# shem.net
KiCad netlist of a schematic drawn in EAGLE
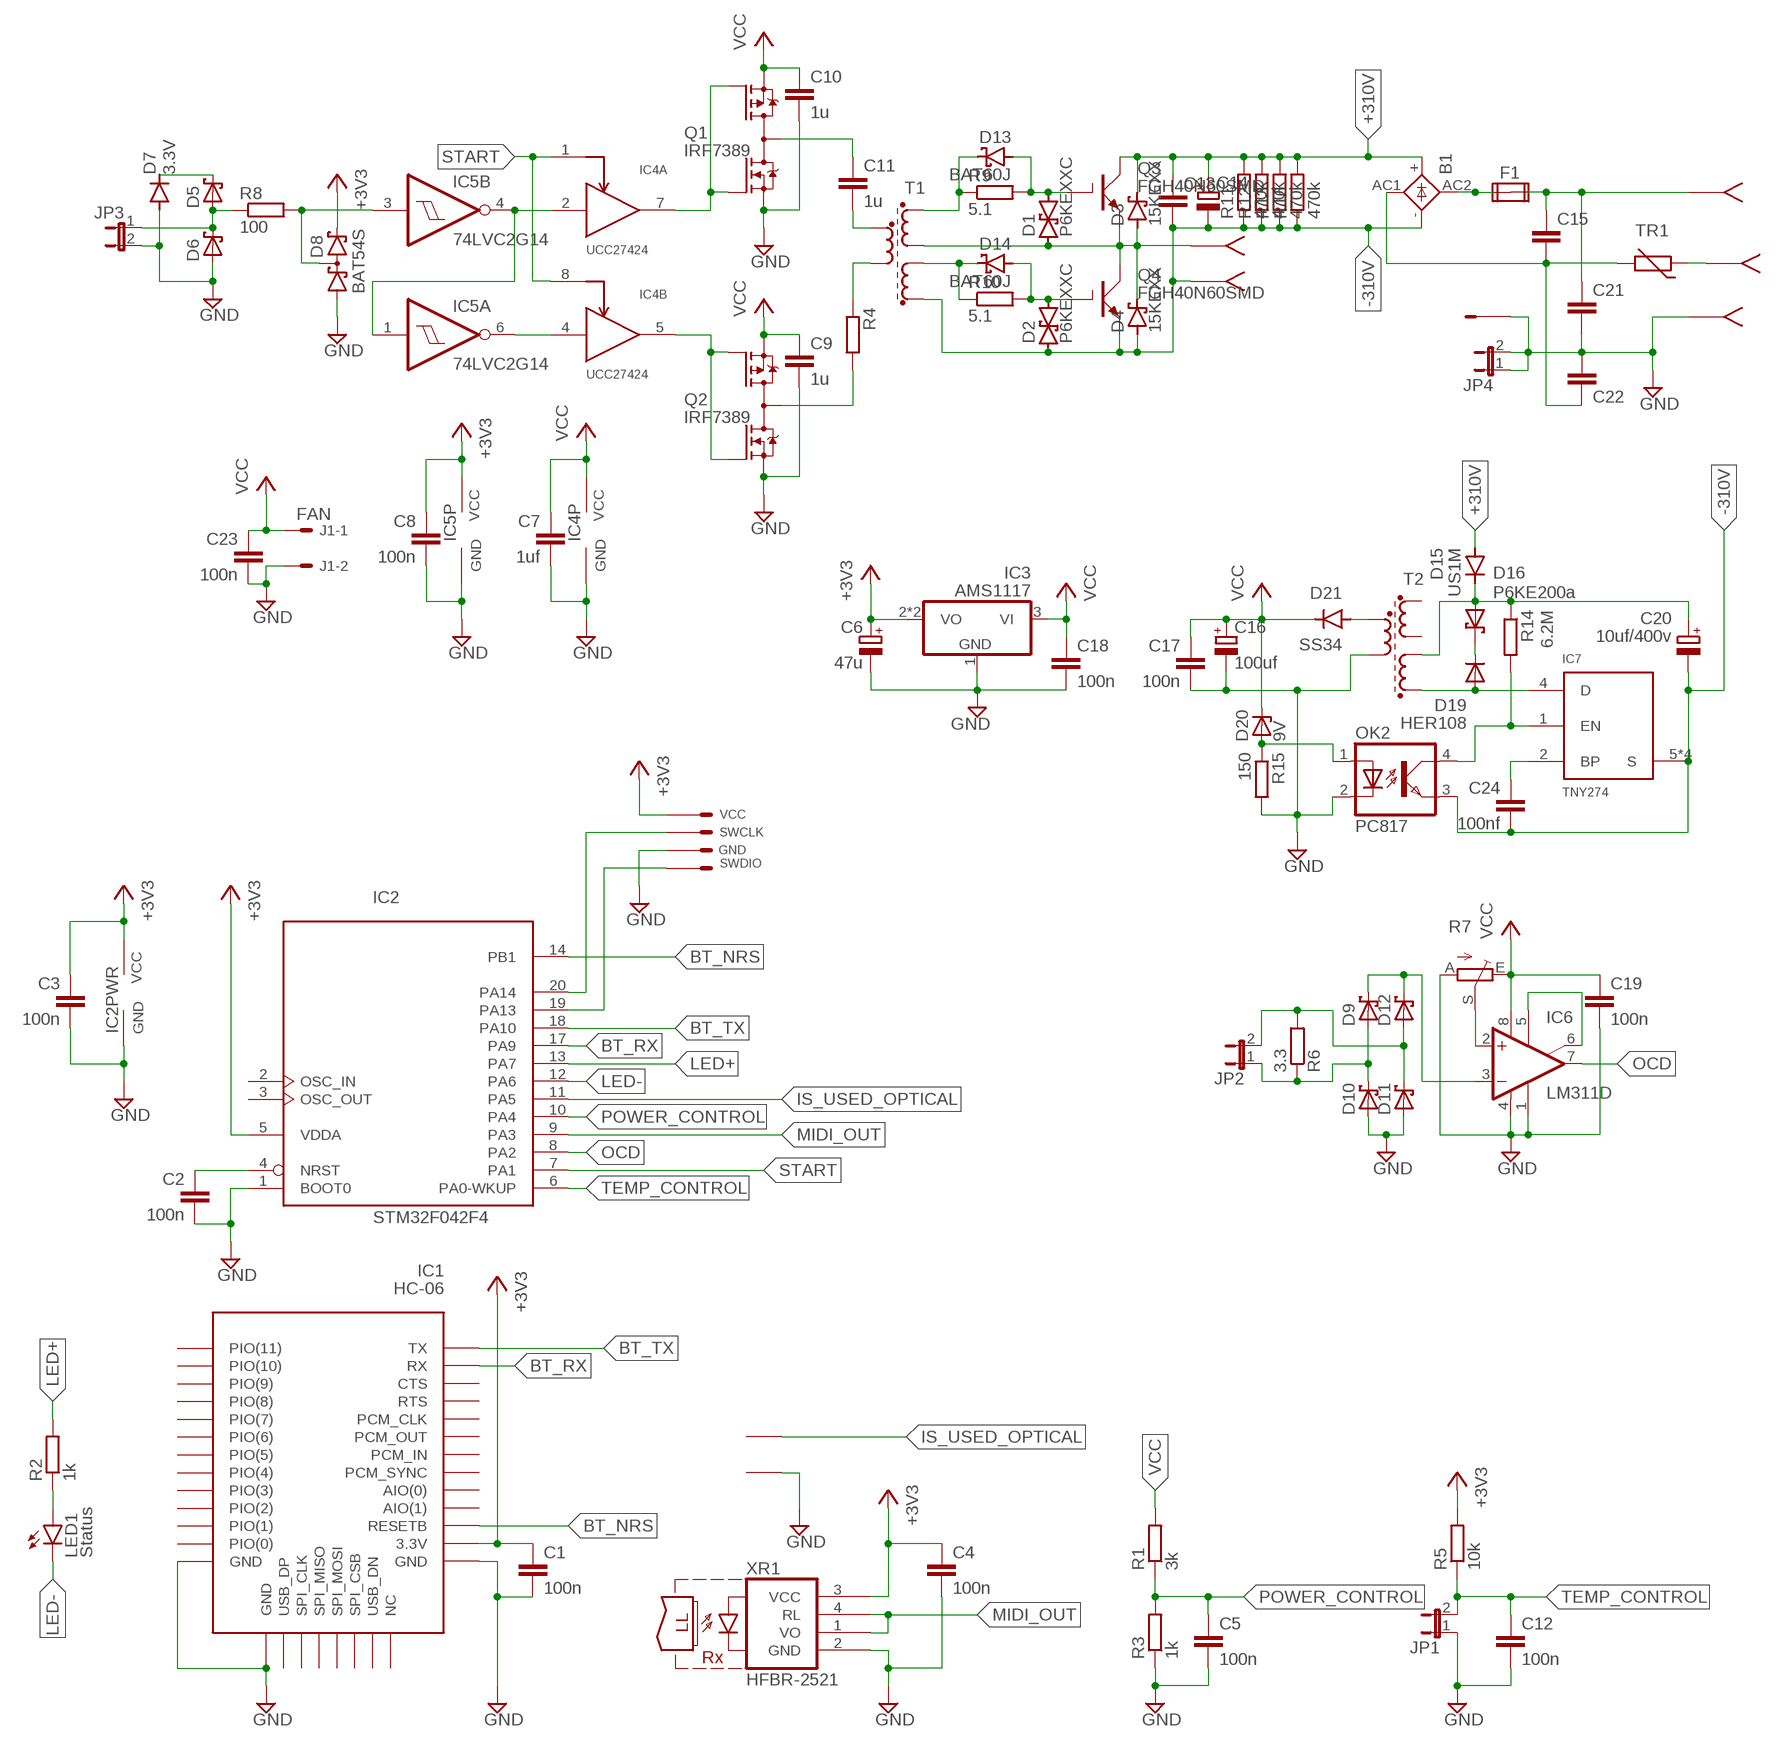
[diagram p0: schematic, sheet 1]

(export (version "E")
  (design (tool "Eeschema 10.0.6"))
  (components
    (comp (ref "B1")
      (value "GBU4")
      (footprint "eagle-import:GBU4S")
      (libsource (lib "eagle-import") (part "GBU4"))
    )
    (comp (ref "C1")
      (value "100n")
      (footprint "eagle-import:C0805")
      (libsource (lib "eagle-import") (part "CAP"))
    )
    (comp (ref "C2")
      (value "100n")
      (footprint "eagle-import:C0805")
      (libsource (lib "eagle-import") (part "CAP"))
    )
    (comp (ref "C3")
      (value "100n")
      (footprint "eagle-import:C0805")
      (libsource (lib "eagle-import") (part "CAP"))
    )
    (comp (ref "C4")
      (value "100n")
      (footprint "eagle-import:C0805")
      (libsource (lib "eagle-import") (part "CAP"))
    )
    (comp (ref "C5")
      (value "100n")
      (footprint "eagle-import:C0805")
      (libsource (lib "eagle-import") (part "CAP"))
    )
    (comp (ref "C6")
      (value "47u")
      (footprint "eagle-import:E2,5-6")
      (libsource (lib "eagle-import") (part "CPOL-EUE2.5-6"))
    )
    (comp (ref "C7")
      (value "1uf")
      (footprint "eagle-import:C0805")
      (libsource (lib "eagle-import") (part "CAP"))
    )
    (comp (ref "C8")
      (value "100n")
      (footprint "eagle-import:C0805")
      (libsource (lib "eagle-import") (part "CAP"))
    )
    (comp (ref "C9")
      (value "1u")
      (footprint "eagle-import:C0805")
      (libsource (lib "eagle-import") (part "CAP"))
    )
    (comp (ref "C10")
      (value "1u")
      (footprint "eagle-import:C0805")
      (libsource (lib "eagle-import") (part "CAP"))
    )
    (comp (ref "C11")
      (value "1u")
      (footprint "eagle-import:C0805")
      (libsource (lib "eagle-import") (part "CAP"))
    )
    (comp (ref "C12")
      (value "100n")
      (footprint "eagle-import:C0805")
      (libsource (lib "eagle-import") (part "CAP"))
    )
    (comp (ref "C13")
      (value "C-EU225-074X268")
      (footprint "eagle-import:C225-074X268")
      (libsource (lib "eagle-import") (part "C-EU225-074X268"))
    )
    (comp (ref "C14")
      (value "CPOL-EUE10-25")
      (footprint "eagle-import:EB25D")
      (libsource (lib "eagle-import") (part "CPOL-EUE10-25"))
    )
    (comp (ref "C15")
      (value "C-EU150-072X183")
      (footprint "eagle-import:C150-072X183")
      (libsource (lib "eagle-import") (part "C-EU150-072X183"))
    )
    (comp (ref "C16")
      (value "100uf")
      (footprint "eagle-import:E2,5-7")
      (libsource (lib "eagle-import") (part "CPOL-EUE2.5-7"))
    )
    (comp (ref "C17")
      (value "100n")
      (footprint "eagle-import:C0805")
      (libsource (lib "eagle-import") (part "CAP"))
    )
    (comp (ref "C18")
      (value "100n")
      (footprint "eagle-import:C0805")
      (libsource (lib "eagle-import") (part "CAP"))
    )
    (comp (ref "C19")
      (value "100n")
      (footprint "eagle-import:C0805")
      (libsource (lib "eagle-import") (part "CAP"))
    )
    (comp (ref "C20")
      (value "10uf/400v")
      (footprint "eagle-import:E3,5-8")
      (libsource (lib "eagle-import") (part "resistor_348_CPOL-EUE3.5-8"))
    )
    (comp (ref "C21")
      (value "CAP_5/7")
      (footprint "eagle-import:C5_7")
      (libsource (lib "eagle-import") (part "CAP_5/7"))
    )
    (comp (ref "C22")
      (value "CAP_5/7")
      (footprint "eagle-import:C5_7")
      (libsource (lib "eagle-import") (part "CAP_5/7"))
    )
    (comp (ref "C23")
      (value "100n")
      (footprint "eagle-import:C0805")
      (libsource (lib "eagle-import") (part "CAP"))
    )
    (comp (ref "C24")
      (value "100nf")
      (footprint "eagle-import:C0805")
      (libsource (lib "eagle-import") (part "CAP"))
    )
    (comp (ref "D1")
      (value "P6KEXXC")
      (footprint "eagle-import:CB417-15")
      (libsource (lib "eagle-import") (part "P6KEXXC"))
    )
    (comp (ref "D2")
      (value "P6KEXXC")
      (footprint "eagle-import:CB417-15")
      (libsource (lib "eagle-import") (part "P6KEXXC"))
    )
    (comp (ref "D3")
      (value "15KEXX")
      (footprint "eagle-import:CB429-17")
      (libsource (lib "eagle-import") (part "15KEXX"))
    )
    (comp (ref "D4")
      (value "15KEXX")
      (footprint "eagle-import:CB429-17")
      (libsource (lib "eagle-import") (part "15KEXX"))
    )
    (comp (ref "D5")
      (value "SHOTTKY_DIODE")
      (footprint "eagle-import:S0D-123")
      (libsource (lib "eagle-import") (part "SHOTTKY_DIODE"))
    )
    (comp (ref "D6")
      (value "SHOTTKY_DIODE")
      (footprint "eagle-import:S0D-123")
      (libsource (lib "eagle-import") (part "SHOTTKY_DIODE"))
    )
    (comp (ref "D7")
      (value "3.3V")
      (footprint "eagle-import:MINIMELF")
      (libsource (lib "eagle-import") (part "DIODE-MINIMELF"))
    )
    (comp (ref "D8")
      (value "BAT54S")
      (footprint "eagle-import:SOT23")
      (libsource (lib "eagle-import") (part "BAS70-04"))
    )
    (comp (ref "D9")
      (value "SHOTTKY_DIODE")
      (footprint "eagle-import:S0D-123")
      (libsource (lib "eagle-import") (part "SHOTTKY_DIODE"))
    )
    (comp (ref "D10")
      (value "SHOTTKY_DIODE")
      (footprint "eagle-import:S0D-123")
      (libsource (lib "eagle-import") (part "SHOTTKY_DIODE"))
    )
    (comp (ref "D11")
      (value "SHOTTKY_DIODE")
      (footprint "eagle-import:S0D-123")
      (libsource (lib "eagle-import") (part "SHOTTKY_DIODE"))
    )
    (comp (ref "D12")
      (value "SHOTTKY_DIODE")
      (footprint "eagle-import:S0D-123")
      (libsource (lib "eagle-import") (part "SHOTTKY_DIODE"))
    )
    (comp (ref "D13")
      (value "BAT60J")
      (footprint "eagle-import:SOD323_ST")
      (libsource (lib "eagle-import") (part "BAT60J"))
    )
    (comp (ref "D14")
      (value "BAT60J")
      (footprint "eagle-import:SOD323_ST")
      (libsource (lib "eagle-import") (part "BAT60J"))
    )
    (comp (ref "D15")
      (value "US1M")
      (footprint "eagle-import:DO-214AC")
      (libsource (lib "eagle-import") (part "DIODE-DO-214AC"))
    )
    (comp (ref "D16")
      (value "P6KE200a")
      (footprint "eagle-import:DO-15W")
      (libsource (lib "eagle-import") (part "SUP_A_DO27'"))
    )
    (comp (ref "D19")
      (value "HER108")
      (footprint "eagle-import:DO-41W")
      (libsource (lib "eagle-import") (part "DIODE_DO-41"))
    )
    (comp (ref "D20")
      (value "9V")
      (footprint "eagle-import:MINIMELF")
      (libsource (lib "eagle-import") (part "ZENER_DIODE{dblquote}{dblquote}"))
    )
    (comp (ref "D21")
      (value "SS34")
      (footprint "eagle-import:DO-214AC")
      (libsource (lib "eagle-import") (part "DIODE-DO-214AC"))
    )
    (comp (ref "F1")
      (value "FUSE2P")
      (footprint "eagle-import:FUSE1")
      (libsource (lib "eagle-import") (part "FUSE2P"))
    )
    (comp (ref "IC1")
      (value "HC-06")
      (footprint "eagle-import:BLUETOOTH")
      (libsource (lib "eagle-import") (part "HC-06"))
    )
    (comp (ref "IC2")
      (value "STM32F042F4")
      (footprint "eagle-import:TSSOP-20")
      (libsource (lib "eagle-import") (part "STM32F030F4"))
    )
    (comp (ref "IC3")
      (value "AMS1117")
      (footprint "eagle-import:SOT223")
      (libsource (lib "eagle-import") (part "AMS1117"))
    )
    (comp (ref "IC4")
      (value "UCC27424")
      (footprint "eagle-import:SO08")
      (libsource (lib "eagle-import") (part "UCC27424"))
    )
    (comp (ref "IC5")
      (value "74LVC2G14")
      (footprint "eagle-import:SOT23-6")
      (libsource (lib "eagle-import") (part "74LVC2G14'"))
    )
    (comp (ref "IC6")
      (value "LM311D")
      (footprint "eagle-import:SO08")
      (libsource (lib "eagle-import") (part "LM311D"))
    )
    (comp (ref "IC7")
      (value "TNY274")
      (footprint "eagle-import:DIL07")
      (libsource (lib "eagle-import") (part "TNY274'''"))
    )
    (comp (ref "J1")
      (value "FAN")
      (footprint "eagle-import:6410-02")
      (fields (field (name "MF") "MOLEX"))
      (libsource (lib "eagle-import") (part "22-?-0227-2021"))
    )
    (comp (ref "JP1")
      (value "JP1E")
      (footprint "eagle-import:JP1")
      (libsource (lib "eagle-import") (part "JP1E"))
    )
    (comp (ref "JP2")
      (value "JP1E")
      (footprint "eagle-import:JP1")
      (libsource (lib "eagle-import") (part "JP1E"))
    )
    (comp (ref "JP3")
      (value "JP1E")
      (footprint "eagle-import:JP1")
      (libsource (lib "eagle-import") (part "JP1E"))
    )
    (comp (ref "JP4")
      (value "JP1E")
      (footprint "eagle-import:JP1")
      (libsource (lib "eagle-import") (part "JP1E"))
    )
    (comp (ref "LED1")
      (value "Status")
      (footprint "eagle-import:LED3MM")
      (libsource (lib "eagle-import") (part "LED3MM"))
    )
    (comp (ref "OK2")
      (value "PC817")
      (footprint "eagle-import:DIL4-SMD")
      (libsource (lib "eagle-import") (part "LTV816S"))
    )
    (comp (ref "Q1")
      (value "IRF7389")
      (footprint "eagle-import:SO08")
      (libsource (lib "eagle-import") (part "IRF7389"))
    )
    (comp (ref "Q2")
      (value "IRF7389")
      (footprint "eagle-import:SO08")
      (libsource (lib "eagle-import") (part "IRF7389"))
    )
    (comp (ref "Q3")
      (value "FGH40N60SMD")
      (footprint "eagle-import:TO247BV")
      (libsource (lib "eagle-import") (part "FGH40N60SMD"))
    )
    (comp (ref "Q4")
      (value "FGH40N60SMD")
      (footprint "eagle-import:TO247BV")
      (libsource (lib "eagle-import") (part "FGH40N60SMD"))
    )
    (comp (ref "R1")
      (value "3k")
      (footprint "eagle-import:R0805")
      (libsource (lib "eagle-import") (part "RES"))
    )
    (comp (ref "R2")
      (value "1k")
      (footprint "eagle-import:R0805")
      (libsource (lib "eagle-import") (part "RES"))
    )
    (comp (ref "R3")
      (value "1k")
      (footprint "eagle-import:R0805")
      (libsource (lib "eagle-import") (part "RES"))
    )
    (comp (ref "R4")
      (value "R-EU_0414/5V")
      (footprint "eagle-import:0414V")
      (libsource (lib "eagle-import") (part "R-EU_0414/5V"))
    )
    (comp (ref "R5")
      (value "10k")
      (footprint "eagle-import:R0805")
      (libsource (lib "eagle-import") (part "RES"))
    )
    (comp (ref "R6")
      (value "3.3")
      (footprint "eagle-import:R0805")
      (libsource (lib "eagle-import") (part "RES"))
    )
    (comp (ref "R7")
      (value "TRIM_EU-B64Y")
      (footprint "eagle-import:B64Y")
      (libsource (lib "eagle-import") (part "TRIM_EU-B64Y"))
    )
    (comp (ref "R8")
      (value "100")
      (footprint "eagle-import:R0805")
      (libsource (lib "eagle-import") (part "RES"))
    )
    (comp (ref "R9")
      (value "5.1")
      (footprint "eagle-import:R0805")
      (libsource (lib "eagle-import") (part "RES"))
    )
    (comp (ref "R10")
      (value "5.1")
      (footprint "eagle-import:R0805")
      (libsource (lib "eagle-import") (part "RES"))
    )
    (comp (ref "R11")
      (value "470k")
      (footprint "eagle-import:1206")
      (libsource (lib "eagle-import") (part "RES_0603{dblquote}{dblquote}"))
    )
    (comp (ref "R12")
      (value "470k")
      (footprint "eagle-import:1206")
      (libsource (lib "eagle-import") (part "RES_0603{dblquote}{dblquote}"))
    )
    (comp (ref "R13")
      (value "470k")
      (footprint "eagle-import:1206")
      (libsource (lib "eagle-import") (part "RES_0603{dblquote}{dblquote}"))
    )
    (comp (ref "R14")
      (value "6.2M")
      (footprint "eagle-import:R0805")
      (libsource (lib "eagle-import") (part "RES"))
    )
    (comp (ref "R15")
      (value "150")
      (footprint "eagle-import:R0805")
      (libsource (lib "eagle-import") (part "RES"))
    )
    (comp (ref "R16")
      (value "470k")
      (footprint "eagle-import:1206")
      (libsource (lib "eagle-import") (part "RES_0603{dblquote}{dblquote}"))
    )
    (comp (ref "T1")
      (value "GDT-2")
      (footprint "eagle-import:GDT-2")
      (libsource (lib "eagle-import") (part "GDT-2"))
    )
    (comp (ref "T2")
      (value "PULSE_TRANS")
      (footprint "eagle-import:PULSE_TRANS")
      (libsource (lib "eagle-import") (part "PULSE_TRANS"))
    )
    (comp (ref "TR1")
      (value "TR")
      (footprint "eagle-import:R-7,5")
      (libsource (lib "eagle-import") (part "TR"))
    )
    (comp (ref "U$1")
      (value "SWD")
      (footprint "eagle-import:SWD")
      (libsource (lib "eagle-import") (part "SWD"))
    )
    (comp (ref "U$2")
      (value "CLEM")
      (footprint "eagle-import:CLEM")
      (libsource (lib "eagle-import") (part "CLEM"))
    )
    (comp (ref "U$3")
      (value "CLEM")
      (footprint "eagle-import:CLEM")
      (libsource (lib "eagle-import") (part "CLEM"))
    )
    (comp (ref "U$4")
      (value "CLEM")
      (footprint "eagle-import:CLEM")
      (libsource (lib "eagle-import") (part "CLEM"))
    )
    (comp (ref "U$5")
      (value "CLEM")
      (footprint "eagle-import:CLEM")
      (libsource (lib "eagle-import") (part "CLEM"))
    )
    (comp (ref "U$6")
      (value "CLEM")
      (footprint "eagle-import:CLEM")
      (libsource (lib "eagle-import") (part "CLEM"))
    )
    (comp (ref "U$7")
      (value "SECONDARY")
      (footprint "eagle-import:SECONDARY")
      (libsource (lib "eagle-import") (part "SECONDARY"))
    )
    (comp (ref "XR1")
      (value "HFBR-2521")
      (footprint "eagle-import:HFBR-15X3")
      (fields (field (name "MF") "AGILENT TECHNOLOGIES"))
      (libsource (lib "eagle-import") (part "HFBR-2521"))
    )
  )
  (nets
    (net (code "1") (name "+3V3") (class "Default")
      (node (ref "C1") (pin "1") (pinfunction "1_1") (pintype "passive"))
      (node (ref "C3") (pin "1") (pinfunction "1_1") (pintype "passive"))
      (node (ref "C4") (pin "1") (pinfunction "1_1") (pintype "passive"))
      (node (ref "C6") (pin "+") (pinfunction "+_+") (pintype "passive"))
      (node (ref "C8") (pin "1") (pinfunction "1_1") (pintype "passive"))
      (node (ref "D8") (pin "2") (pinfunction "C2_2") (pintype "passive"))
      (node (ref "IC1") (pin "12") (pinfunction "3.3V_12") (pintype "bidirectional"))
      (node (ref "IC2") (pin "16") (pinfunction "VCC_16") (pintype "power_in"))
      (node (ref "IC2") (pin "5") (pinfunction "VDDA_5") (pintype "power_in"))
      (node (ref "IC3") (pin "2") (pinfunction "VO_2") (pintype "power_in"))
      (node (ref "IC3") (pin "4") (pinfunction "VO_4") (pintype "power_in"))
      (node (ref "IC5") (pin "5") (pinfunction "VCC_5") (pintype "power_in"))
      (node (ref "R5") (pin "2") (pinfunction "2_2") (pintype "passive"))
      (node (ref "U$1") (pin "VCC") (pinfunction "VCC_VCC") (pintype "power_in"))
      (node (ref "XR1") (pin "3") (pinfunction "VCC_3") (pintype "power_in"))
    )
    (net (code "2") (name "+310V") (class "Default")
      (node (ref "B1") (pin "+") (pinfunction "+_+") (pintype "passive"))
      (node (ref "C13") (pin "1") (pinfunction "1_1") (pintype "passive"))
      (node (ref "C14") (pin "+") (pinfunction "+_+") (pintype "passive"))
      (node (ref "D15") (pin "A") (pinfunction "A_A") (pintype "passive"))
      (node (ref "D3") (pin "C") (pinfunction "C_C") (pintype "passive"))
      (node (ref "Q3") (pin "D") (pinfunction "C_D") (pintype "passive"))
      (node (ref "R11") (pin "2") (pinfunction "2_2") (pintype "passive"))
      (node (ref "R12") (pin "2") (pinfunction "2_2") (pintype "passive"))
      (node (ref "R13") (pin "2") (pinfunction "2_2") (pintype "passive"))
      (node (ref "R16") (pin "2") (pinfunction "2_2") (pintype "passive"))
    )
    (net (code "3") (name "-310V") (class "Default")
      (node (ref "B1") (pin "-") (pinfunction "-_-") (pintype "passive"))
      (node (ref "C13") (pin "2") (pinfunction "2_2") (pintype "passive"))
      (node (ref "C14") (pin "-") (pinfunction "-_-") (pintype "passive"))
      (node (ref "C20") (pin "-") (pinfunction "-_-") (pintype "passive"))
      (node (ref "C24") (pin "2") (pinfunction "2_2") (pintype "passive"))
      (node (ref "D2") (pin "A") (pinfunction "1_A") (pintype "passive"))
      (node (ref "D4") (pin "A") (pinfunction "A_A") (pintype "passive"))
      (node (ref "IC7") (pin "5") (pinfunction "S_5") (pintype "passive"))
      (node (ref "IC7") (pin "6") (pinfunction "S_6") (pintype "passive"))
      (node (ref "IC7") (pin "7") (pinfunction "S_7") (pintype "passive"))
      (node (ref "IC7") (pin "8") (pinfunction "S_8") (pintype "passive"))
      (node (ref "OK2") (pin "3") (pinfunction "EMIT_3") (pintype "passive"))
      (node (ref "Q4") (pin "S") (pinfunction "E_S") (pintype "passive"))
      (node (ref "R11") (pin "1") (pinfunction "1_1") (pintype "passive"))
      (node (ref "R12") (pin "1") (pinfunction "1_1") (pintype "passive"))
      (node (ref "R13") (pin "1") (pinfunction "1_1") (pintype "passive"))
      (node (ref "R16") (pin "1") (pinfunction "1_1") (pintype "passive"))
      (node (ref "T1") (pin "OUT2A") (pinfunction "OUT2A_OUT2A") (pintype "passive"))
      (node (ref "U$3") (pin "P$1") (pinfunction "P$1_P$1") (pintype "passive"))
      (node (ref "U$3") (pin "P$2") (pinfunction "P$1_P$2") (pintype "passive"))
    )
    (net (code "4") (name "BT_NRS") (class "Default")
      (node (ref "IC1") (pin "11") (pinfunction "RESETB_11") (pintype "bidirectional"))
      (node (ref "IC2") (pin "14") (pinfunction "PB1_14") (pintype "bidirectional"))
    )
    (net (code "5") (name "BT_RX") (class "Default")
      (node (ref "IC1") (pin "2") (pinfunction "RX_2") (pintype "bidirectional"))
      (node (ref "IC2") (pin "17") (pinfunction "PA9_17") (pintype "bidirectional"))
    )
    (net (code "6") (name "BT_TX") (class "Default")
      (node (ref "IC1") (pin "1") (pinfunction "TX_1") (pintype "bidirectional"))
      (node (ref "IC2") (pin "18") (pinfunction "PA10_18") (pintype "bidirectional"))
    )
    (net (code "7") (name "GND") (class "Default")
      (node (ref "C1") (pin "2") (pinfunction "2_2") (pintype "passive"))
      (node (ref "C10") (pin "2") (pinfunction "2_2") (pintype "passive"))
      (node (ref "C12") (pin "2") (pinfunction "2_2") (pintype "passive"))
      (node (ref "C16") (pin "-") (pinfunction "-_-") (pintype "passive"))
      (node (ref "C17") (pin "2") (pinfunction "2_2") (pintype "passive"))
      (node (ref "C18") (pin "2") (pinfunction "2_2") (pintype "passive"))
      (node (ref "C19") (pin "2") (pinfunction "2_2") (pintype "passive"))
      (node (ref "C2") (pin "2") (pinfunction "2_2") (pintype "passive"))
      (node (ref "C21") (pin "2") (pinfunction "2_2") (pintype "passive"))
      (node (ref "C21") (pin "3") (pinfunction "2_3") (pintype "passive"))
      (node (ref "C22") (pin "2") (pinfunction "2_2") (pintype "passive"))
      (node (ref "C22") (pin "3") (pinfunction "2_3") (pintype "passive"))
      (node (ref "C23") (pin "2") (pinfunction "2_2") (pintype "passive"))
      (node (ref "C3") (pin "2") (pinfunction "2_2") (pintype "passive"))
      (node (ref "C4") (pin "2") (pinfunction "2_2") (pintype "passive"))
      (node (ref "C5") (pin "2") (pinfunction "2_2") (pintype "passive"))
      (node (ref "C6") (pin "-") (pinfunction "-_-") (pintype "passive"))
      (node (ref "C7") (pin "2") (pinfunction "2_2") (pintype "passive"))
      (node (ref "C8") (pin "2") (pinfunction "2_2") (pintype "passive"))
      (node (ref "C9") (pin "2") (pinfunction "2_2") (pintype "passive"))
      (node (ref "D10") (pin "A") (pinfunction "A_A") (pintype "passive"))
      (node (ref "D11") (pin "A") (pinfunction "A_A") (pintype "passive"))
      (node (ref "D6") (pin "A") (pinfunction "A_A") (pintype "passive"))
      (node (ref "D7") (pin "A") (pinfunction "A_A") (pintype "passive"))
      (node (ref "D8") (pin "1") (pinfunction "A1_1") (pintype "passive"))
      (node (ref "IC1") (pin "13") (pinfunction "GND_13") (pintype "bidirectional"))
      (node (ref "IC1") (pin "21") (pinfunction "GND_21") (pintype "bidirectional"))
      (node (ref "IC1") (pin "22") (pinfunction "GND_22") (pintype "bidirectional"))
      (node (ref "IC2") (pin "1") (pinfunction "BOOT0_1") (pintype "input"))
      (node (ref "IC2") (pin "15") (pinfunction "GND_15") (pintype "power_in"))
      (node (ref "IC3") (pin "1") (pinfunction "GND_1") (pintype "power_in"))
      (node (ref "IC4") (pin "3") (pinfunction "GND_3") (pintype "power_in"))
      (node (ref "IC5") (pin "2") (pinfunction "GND_2") (pintype "power_in"))
      (node (ref "IC6") (pin "1") (pinfunction "GND_1") (pintype "passive"))
      (node (ref "IC6") (pin "4") (pinfunction "V-_4") (pintype "power_in"))
      (node (ref "J1") (pin "2") (pinfunction "S_2") (pintype "passive"))
      (node (ref "JP1") (pin "1") (pinfunction "1_1") (pintype "passive"))
      (node (ref "JP3") (pin "2") (pinfunction "2_2") (pintype "passive"))
      (node (ref "JP4") (pin "1") (pinfunction "1_1") (pintype "passive"))
      (node (ref "JP4") (pin "2") (pinfunction "2_2") (pintype "passive"))
      (node (ref "OK2") (pin "2") (pinfunction "C_2") (pintype "passive"))
      (node (ref "Q1") (pin "1") (pinfunction "N-S_1") (pintype "passive"))
      (node (ref "Q2") (pin "1") (pinfunction "N-S_1") (pintype "passive"))
      (node (ref "R15") (pin "2") (pinfunction "2_2") (pintype "passive"))
      (node (ref "R3") (pin "1") (pinfunction "1_1") (pintype "passive"))
      (node (ref "R7") (pin "A") (pinfunction "A_A") (pintype "passive"))
      (node (ref "T2") (pin "C2") (pinfunction "C2_C2") (pintype "passive"))
      (node (ref "U$1") (pin "GND") (pinfunction "GND_GND") (pintype "power_in"))
      (node (ref "U$6") (pin "P$1") (pinfunction "P$1_P$1") (pintype "passive"))
      (node (ref "U$6") (pin "P$2") (pinfunction "P$1_P$2") (pintype "passive"))
      (node (ref "U$7") (pin "1") (pinfunction "1_1") (pintype "bidirectional"))
      (node (ref "XR1") (pin "2") (pinfunction "GND_2") (pintype "power_in"))
      (node (ref "XR1") (pin "5") (pinfunction "P$1_5") (pintype "bidirectional"))
    )
    (net (code "8") (name "IS_USED_OPTICAL") (class "Default")
      (node (ref "IC2") (pin "11") (pinfunction "PA5_11") (pintype "bidirectional"))
      (node (ref "XR1") (pin "8") (pinfunction "P$1_8") (pintype "bidirectional"))
    )
    (net (code "9") (name "LED+") (class "Default")
      (node (ref "IC2") (pin "13") (pinfunction "PA7_13") (pintype "bidirectional"))
      (node (ref "R2") (pin "2") (pinfunction "2_2") (pintype "passive"))
    )
    (net (code "10") (name "LED-") (class "Default")
      (node (ref "IC2") (pin "12") (pinfunction "PA6_12") (pintype "bidirectional"))
      (node (ref "LED1") (pin "K") (pinfunction "C_K") (pintype "passive"))
    )
    (net (code "11") (name "MIDI_OUT") (class "Default")
      (node (ref "IC2") (pin "9") (pinfunction "PA3_9") (pintype "bidirectional"))
      (node (ref "XR1") (pin "1") (pinfunction "VO_1") (pintype "passive"))
      (node (ref "XR1") (pin "4") (pinfunction "RL_4") (pintype "passive"))
    )
    (net (code "12") (name "Net-(B1-AC1)") (class "Default")
      (node (ref "B1") (pin "AC2") (pinfunction "AC1_AC2") (pintype "passive"))
      (node (ref "F1") (pin "2A") (pinfunction "2A_2A") (pintype "passive"))
      (node (ref "F1") (pin "2B") (pinfunction "2B_2B") (pintype "passive"))
    )
    (net (code "13") (name "Net-(B1-AC2)") (class "Default")
      (node (ref "B1") (pin "AC1") (pinfunction "AC2_AC1") (pintype "passive"))
      (node (ref "C15") (pin "2") (pinfunction "2_2") (pintype "passive"))
      (node (ref "C22") (pin "1") (pinfunction "1_1") (pintype "passive"))
      (node (ref "TR1") (pin "2") (pinfunction "2_2") (pintype "passive"))
    )
    (net (code "14") (name "Net-(C11-Pad1)") (class "Default")
      (node (ref "C11") (pin "1") (pinfunction "1_1") (pintype "passive"))
      (node (ref "Q1") (pin "5") (pinfunction "D_5") (pintype "passive"))
      (node (ref "Q1") (pin "6") (pinfunction "D_6") (pintype "passive"))
      (node (ref "Q1") (pin "7") (pinfunction "D_7") (pintype "passive"))
      (node (ref "Q1") (pin "8") (pinfunction "D_8") (pintype "passive"))
    )
    (net (code "15") (name "Net-(C15-Pad1)") (class "Default")
      (node (ref "C15") (pin "1") (pinfunction "1_1") (pintype "passive"))
      (node (ref "C21") (pin "1") (pinfunction "1_1") (pintype "passive"))
      (node (ref "F1") (pin "1A") (pinfunction "1A_1A") (pintype "passive"))
      (node (ref "F1") (pin "1B") (pinfunction "1B_1B") (pintype "passive"))
      (node (ref "U$4") (pin "P$1") (pinfunction "P$1_P$1") (pintype "passive"))
      (node (ref "U$4") (pin "P$2") (pinfunction "P$1_P$2") (pintype "passive"))
    )
    (net (code "16") (name "Net-(C20-Pad+)") (class "Default")
      (node (ref "C20") (pin "+") (pinfunction "+_+") (pintype "passive"))
      (node (ref "D15") (pin "C") (pinfunction "C_C") (pintype "passive"))
      (node (ref "D16") (pin "A") (pinfunction "A_A") (pintype "passive"))
      (node (ref "R14") (pin "1") (pinfunction "1_1") (pintype "passive"))
      (node (ref "T2") (pin "B1") (pinfunction "B1_B1") (pintype "passive"))
    )
    (net (code "17") (name "Net-(D1-1)") (class "Default")
      (node (ref "D1") (pin "A") (pinfunction "1_A") (pintype "passive"))
      (node (ref "D3") (pin "A") (pinfunction "A_A") (pintype "passive"))
      (node (ref "D4") (pin "C") (pinfunction "C_C") (pintype "passive"))
      (node (ref "Q3") (pin "S") (pinfunction "E_S") (pintype "passive"))
      (node (ref "Q4") (pin "D") (pinfunction "C_D") (pintype "passive"))
      (node (ref "T1") (pin "OUT1B") (pinfunction "OUT1B_OUT1B") (pintype "passive"))
      (node (ref "U$2") (pin "P$1") (pinfunction "P$1_P$1") (pintype "passive"))
      (node (ref "U$2") (pin "P$2") (pinfunction "P$1_P$2") (pintype "passive"))
    )
    (net (code "18") (name "Net-(D1-2)") (class "Default")
      (node (ref "D1") (pin "C") (pinfunction "2_C") (pintype "passive"))
      (node (ref "D13") (pin "A") (pinfunction "A_A") (pintype "passive"))
      (node (ref "Q3") (pin "G") (pinfunction "G_G") (pintype "passive"))
      (node (ref "R9") (pin "2") (pinfunction "2_2") (pintype "passive"))
    )
    (net (code "19") (name "Net-(D2-2)") (class "Default")
      (node (ref "D14") (pin "A") (pinfunction "A_A") (pintype "passive"))
      (node (ref "D2") (pin "C") (pinfunction "2_C") (pintype "passive"))
      (node (ref "Q4") (pin "G") (pinfunction "G_G") (pintype "passive"))
      (node (ref "R10") (pin "2") (pinfunction "2_2") (pintype "passive"))
    )
    (net (code "20") (name "Net-(D5-PadA)") (class "Default")
      (node (ref "D5") (pin "A") (pinfunction "A_A") (pintype "passive"))
      (node (ref "D6") (pin "C") (pinfunction "C_C") (pintype "passive"))
      (node (ref "JP3") (pin "1") (pinfunction "1_1") (pintype "passive"))
      (node (ref "R8") (pin "1") (pinfunction "1_1") (pintype "passive"))
    )
    (net (code "21") (name "Net-(D5-PadC)") (class "Default")
      (node (ref "D5") (pin "C") (pinfunction "C_C") (pintype "passive"))
      (node (ref "D7") (pin "C") (pinfunction "C_C") (pintype "passive"))
    )
    (net (code "22") (name "Net-(D8-C1A2)") (class "Default")
      (node (ref "D8") (pin "3") (pinfunction "C1A2_3") (pintype "passive"))
      (node (ref "IC5") (pin "3") (pinfunction "I_3") (pintype "input"))
      (node (ref "R8") (pin "2") (pinfunction "2_2") (pintype "passive"))
    )
    (net (code "23") (name "Net-(D10-PadC)") (class "Default")
      (node (ref "D10") (pin "C") (pinfunction "C_C") (pintype "passive"))
      (node (ref "D9") (pin "A") (pinfunction "A_A") (pintype "passive"))
      (node (ref "JP2") (pin "1") (pinfunction "1_1") (pintype "passive"))
      (node (ref "R6") (pin "1") (pinfunction "1_1") (pintype "passive"))
    )
    (net (code "24") (name "Net-(D11-PadC)") (class "Default")
      (node (ref "D11") (pin "C") (pinfunction "C_C") (pintype "passive"))
      (node (ref "D12") (pin "A") (pinfunction "A_A") (pintype "passive"))
      (node (ref "JP2") (pin "2") (pinfunction "2_2") (pintype "passive"))
      (node (ref "R6") (pin "2") (pinfunction "2_2") (pintype "passive"))
    )
    (net (code "25") (name "Net-(D13-PadC)") (class "Default")
      (node (ref "D13") (pin "C") (pinfunction "C_C") (pintype "passive"))
      (node (ref "R9") (pin "1") (pinfunction "1_1") (pintype "passive"))
      (node (ref "T1") (pin "OUT1A") (pinfunction "OUT1A_OUT1A") (pintype "passive"))
    )
    (net (code "26") (name "Net-(D14-PadC)") (class "Default")
      (node (ref "D14") (pin "C") (pinfunction "C_C") (pintype "passive"))
      (node (ref "R10") (pin "1") (pinfunction "1_1") (pintype "passive"))
      (node (ref "T1") (pin "OUT2B") (pinfunction "OUT2B_OUT2B") (pintype "passive"))
    )
    (net (code "27") (name "Net-(D16-PadC)") (class "Default")
      (node (ref "D16") (pin "C") (pinfunction "C_C") (pintype "passive"))
      (node (ref "D19") (pin "C") (pinfunction "C_C") (pintype "passive"))
    )
    (net (code "28") (name "Net-(D21-PadA)") (class "Default")
      (node (ref "D21") (pin "A") (pinfunction "A_A") (pintype "passive"))
      (node (ref "T2") (pin "C1") (pinfunction "C1_C1") (pintype "passive"))
    )
    (net (code "29") (name "Net-(IC2A-NRST)") (class "Default")
      (node (ref "C2") (pin "1") (pinfunction "1_1") (pintype "passive"))
      (node (ref "IC2") (pin "4") (pinfunction "NRST_4") (pintype "bidirectional"))
    )
    (net (code "30") (name "Net-(IC2A-PA13)") (class "Default")
      (node (ref "IC2") (pin "19") (pinfunction "PA13_19") (pintype "bidirectional"))
      (node (ref "U$1") (pin "SWDIO") (pinfunction "SWDIO_SWDIO") (pintype "bidirectional"))
    )
    (net (code "31") (name "Net-(IC2A-PA14)") (class "Default")
      (node (ref "IC2") (pin "20") (pinfunction "PA14_20") (pintype "bidirectional"))
      (node (ref "U$1") (pin "SWCLK") (pinfunction "SWCLK_SWCLK") (pintype "bidirectional"))
    )
    (net (code "32") (name "Net-(IC4A-IN)") (class "Default")
      (node (ref "IC4") (pin "2") (pinfunction "IN_2") (pintype "input"))
      (node (ref "IC5") (pin "1") (pinfunction "I_1") (pintype "input"))
      (node (ref "IC5") (pin "4") (pinfunction "O_4") (pintype "output"))
    )
    (net (code "33") (name "Net-(IC4A-OUT)") (class "Default")
      (node (ref "IC4") (pin "7") (pinfunction "OUT_7") (pintype "output"))
      (node (ref "Q1") (pin "2") (pinfunction "N-G_2") (pintype "passive"))
      (node (ref "Q1") (pin "4") (pinfunction "P-G_4") (pintype "passive"))
    )
    (net (code "34") (name "Net-(IC4B-IN)") (class "Default")
      (node (ref "IC4") (pin "4") (pinfunction "IN_4") (pintype "input"))
      (node (ref "IC5") (pin "6") (pinfunction "O_6") (pintype "output"))
    )
    (net (code "35") (name "Net-(IC4B-OUT)") (class "Default")
      (node (ref "IC4") (pin "5") (pinfunction "OUT_5") (pintype "output"))
      (node (ref "Q2") (pin "2") (pinfunction "N-G_2") (pintype "passive"))
      (node (ref "Q2") (pin "4") (pinfunction "P-G_4") (pintype "passive"))
    )
    (net (code "36") (name "Net-(IC6-+IN)") (class "Default")
      (node (ref "IC6") (pin "2") (pinfunction "+IN_2") (pintype "input"))
      (node (ref "R7") (pin "S") (pinfunction "S_S") (pintype "passive"))
    )
    (net (code "37") (name "Net-(IC6--IN)") (class "Default")
      (node (ref "D12") (pin "C") (pinfunction "C_C") (pintype "passive"))
      (node (ref "D9") (pin "C") (pinfunction "C_C") (pintype "passive"))
      (node (ref "IC6") (pin "3") (pinfunction "-IN_3") (pintype "input"))
    )
    (net (code "38") (name "Net-(IC6-ON)") (class "Default")
      (node (ref "IC6") (pin "5") (pinfunction "ON_5") (pintype "passive"))
      (node (ref "IC6") (pin "6") (pinfunction "ON/STR_6") (pintype "passive"))
    )
    (net (code "39") (name "Net-(IC7-BP)") (class "Default")
      (node (ref "C24") (pin "1") (pinfunction "1_1") (pintype "passive"))
      (node (ref "IC7") (pin "2") (pinfunction "BP_2") (pintype "passive"))
    )
    (net (code "40") (name "Net-(IC7-D)") (class "Default")
      (node (ref "D19") (pin "A") (pinfunction "A_A") (pintype "passive"))
      (node (ref "IC7") (pin "4") (pinfunction "D_4") (pintype "output"))
      (node (ref "T2") (pin "B2") (pinfunction "B2_B2") (pintype "passive"))
    )
    (net (code "41") (name "Net-(IC7-EN)") (class "Default")
      (node (ref "IC7") (pin "1") (pinfunction "EN_1") (pintype "input"))
      (node (ref "OK2") (pin "4") (pinfunction "COL_4") (pintype "passive"))
      (node (ref "R14") (pin "2") (pinfunction "2_2") (pintype "passive"))
    )
    (net (code "42") (name "Net-(LED1-PadA)") (class "Default")
      (node (ref "LED1") (pin "A") (pinfunction "A_A") (pintype "passive"))
      (node (ref "R2") (pin "1") (pinfunction "1_1") (pintype "passive"))
    )
    (net (code "43") (name "Net-(OK2-A)") (class "Default")
      (node (ref "D20") (pin "A") (pinfunction "A_A") (pintype "passive"))
      (node (ref "OK2") (pin "1") (pinfunction "A_1") (pintype "passive"))
      (node (ref "R15") (pin "1") (pinfunction "1_1") (pintype "passive"))
    )
    (net (code "44") (name "Net-(Q2-D-Pad5)") (class "Default")
      (node (ref "Q2") (pin "5") (pinfunction "D_5") (pintype "passive"))
      (node (ref "Q2") (pin "6") (pinfunction "D_6") (pintype "passive"))
      (node (ref "Q2") (pin "7") (pinfunction "D_7") (pintype "passive"))
      (node (ref "Q2") (pin "8") (pinfunction "D_8") (pintype "passive"))
      (node (ref "R4") (pin "2") (pinfunction "2_2") (pintype "passive"))
    )
    (net (code "45") (name "Net-(T1-INA)") (class "Default")
      (node (ref "C11") (pin "2") (pinfunction "2_2") (pintype "passive"))
      (node (ref "T1") (pin "IN_B") (pinfunction "INA_IN_B") (pintype "passive"))
    )
    (net (code "46") (name "Net-(T1-IN_B)") (class "Default")
      (node (ref "R4") (pin "1") (pinfunction "1_1") (pintype "passive"))
      (node (ref "T1") (pin "IN_A") (pinfunction "IN_B_IN_A") (pintype "passive"))
    )
    (net (code "47") (name "Net-(TR1-Pad1)") (class "Default")
      (node (ref "TR1") (pin "1") (pinfunction "1_1") (pintype "passive"))
      (node (ref "U$5") (pin "P$1") (pinfunction "P$1_P$1") (pintype "passive"))
      (node (ref "U$5") (pin "P$2") (pinfunction "P$1_P$2") (pintype "passive"))
    )
    (net (code "48") (name "OCD") (class "Default")
      (node (ref "IC2") (pin "8") (pinfunction "PA2_8") (pintype "bidirectional"))
      (node (ref "IC6") (pin "7") (pinfunction "OUT_7") (pintype "output"))
    )
    (net (code "49") (name "POWER_CONTROL") (class "Default")
      (node (ref "C5") (pin "1") (pinfunction "1_1") (pintype "passive"))
      (node (ref "IC2") (pin "10") (pinfunction "PA4_10") (pintype "bidirectional"))
      (node (ref "R1") (pin "1") (pinfunction "1_1") (pintype "passive"))
      (node (ref "R3") (pin "2") (pinfunction "2_2") (pintype "passive"))
    )
    (net (code "50") (name "START") (class "Default")
      (node (ref "IC2") (pin "7") (pinfunction "PA1_7") (pintype "bidirectional"))
      (node (ref "IC4") (pin "1") (pinfunction "ENB_1") (pintype "input"))
      (node (ref "IC4") (pin "8") (pinfunction "ENB_8") (pintype "input"))
    )
    (net (code "51") (name "TEMP_CONTROL") (class "Default")
      (node (ref "C12") (pin "1") (pinfunction "1_1") (pintype "passive"))
      (node (ref "IC2") (pin "6") (pinfunction "PA0-WKUP_6") (pintype "bidirectional"))
      (node (ref "JP1") (pin "2") (pinfunction "2_2") (pintype "passive"))
      (node (ref "R5") (pin "1") (pinfunction "1_1") (pintype "passive"))
    )
    (net (code "52") (name "VCC") (class "Default")
      (node (ref "C10") (pin "1") (pinfunction "1_1") (pintype "passive"))
      (node (ref "C16") (pin "+") (pinfunction "+_+") (pintype "passive"))
      (node (ref "C17") (pin "1") (pinfunction "1_1") (pintype "passive"))
      (node (ref "C18") (pin "1") (pinfunction "1_1") (pintype "passive"))
      (node (ref "C19") (pin "1") (pinfunction "1_1") (pintype "passive"))
      (node (ref "C23") (pin "1") (pinfunction "1_1") (pintype "passive"))
      (node (ref "C7") (pin "1") (pinfunction "1_1") (pintype "passive"))
      (node (ref "C9") (pin "1") (pinfunction "1_1") (pintype "passive"))
      (node (ref "D20") (pin "C") (pinfunction "C_C") (pintype "passive"))
      (node (ref "D21") (pin "C") (pinfunction "C_C") (pintype "passive"))
      (node (ref "IC3") (pin "3") (pinfunction "VI_3") (pintype "input"))
      (node (ref "IC4") (pin "6") (pinfunction "VCC_6") (pintype "power_in"))
      (node (ref "IC6") (pin "8") (pinfunction "V+_8") (pintype "power_in"))
      (node (ref "J1") (pin "1") (pinfunction "S_1") (pintype "passive"))
      (node (ref "Q1") (pin "3") (pinfunction "P-S_3") (pintype "passive"))
      (node (ref "Q2") (pin "3") (pinfunction "P-S_3") (pintype "passive"))
      (node (ref "R1") (pin "2") (pinfunction "2_2") (pintype "passive"))
      (node (ref "R7") (pin "E") (pinfunction "E_E") (pintype "passive"))
    )
    (net (code "53") (name "unconnected-(IC1-AIO(0)-Pad9)") (class "Default")
      (node (ref "IC1") (pin "9") (pinfunction "AIO(0)_9") (pintype "bidirectional"))
    )
    (net (code "54") (name "unconnected-(IC1-AIO(1)-Pad10)") (class "Default")
      (node (ref "IC1") (pin "10") (pinfunction "AIO(1)_10") (pintype "bidirectional"))
    )
    (net (code "55") (name "unconnected-(IC1-CTS-Pad3)") (class "Default")
      (node (ref "IC1") (pin "3") (pinfunction "CTS_3") (pintype "bidirectional"))
    )
    (net (code "56") (name "unconnected-(IC1-NC-Pad14)") (class "Default")
      (node (ref "IC1") (pin "14") (pinfunction "NC_14") (pintype "bidirectional"))
    )
    (net (code "57") (name "unconnected-(IC1-PCM_CLK-Pad5)") (class "Default")
      (node (ref "IC1") (pin "5") (pinfunction "PCM_CLK_5") (pintype "bidirectional"))
    )
    (net (code "58") (name "unconnected-(IC1-PCM_IN-Pad7)") (class "Default")
      (node (ref "IC1") (pin "7") (pinfunction "PCM_IN_7") (pintype "bidirectional"))
    )
    (net (code "59") (name "unconnected-(IC1-PCM_OUT-Pad6)") (class "Default")
      (node (ref "IC1") (pin "6") (pinfunction "PCM_OUT_6") (pintype "bidirectional"))
    )
    (net (code "60") (name "unconnected-(IC1-PCM_SYNC-Pad8)") (class "Default")
      (node (ref "IC1") (pin "8") (pinfunction "PCM_SYNC_8") (pintype "bidirectional"))
    )
    (net (code "61") (name "unconnected-(IC1-PIO(0)-Pad23)") (class "Default")
      (node (ref "IC1") (pin "23") (pinfunction "PIO(0)_23") (pintype "bidirectional"))
    )
    (net (code "62") (name "unconnected-(IC1-PIO(1)-Pad24)") (class "Default")
      (node (ref "IC1") (pin "24") (pinfunction "PIO(1)_24") (pintype "bidirectional"))
    )
    (net (code "63") (name "unconnected-(IC1-PIO(2)-Pad25)") (class "Default")
      (node (ref "IC1") (pin "25") (pinfunction "PIO(2)_25") (pintype "bidirectional"))
    )
    (net (code "64") (name "unconnected-(IC1-PIO(3)-Pad26)") (class "Default")
      (node (ref "IC1") (pin "26") (pinfunction "PIO(3)_26") (pintype "bidirectional"))
    )
    (net (code "65") (name "unconnected-(IC1-PIO(4)-Pad27)") (class "Default")
      (node (ref "IC1") (pin "27") (pinfunction "PIO(4)_27") (pintype "bidirectional"))
    )
    (net (code "66") (name "unconnected-(IC1-PIO(5)-Pad28)") (class "Default")
      (node (ref "IC1") (pin "28") (pinfunction "PIO(5)_28") (pintype "bidirectional"))
    )
    (net (code "67") (name "unconnected-(IC1-PIO(6)-Pad29)") (class "Default")
      (node (ref "IC1") (pin "29") (pinfunction "PIO(6)_29") (pintype "bidirectional"))
    )
    (net (code "68") (name "unconnected-(IC1-PIO(7)-Pad30)") (class "Default")
      (node (ref "IC1") (pin "30") (pinfunction "PIO(7)_30") (pintype "bidirectional"))
    )
    (net (code "69") (name "unconnected-(IC1-PIO(8)-Pad31)") (class "Default")
      (node (ref "IC1") (pin "31") (pinfunction "PIO(8)_31") (pintype "bidirectional"))
    )
    (net (code "70") (name "unconnected-(IC1-PIO(9)-Pad32)") (class "Default")
      (node (ref "IC1") (pin "32") (pinfunction "PIO(9)_32") (pintype "bidirectional"))
    )
    (net (code "71") (name "unconnected-(IC1-PIO(10)-Pad33)") (class "Default")
      (node (ref "IC1") (pin "33") (pinfunction "PIO(10)_33") (pintype "bidirectional"))
    )
    (net (code "72") (name "unconnected-(IC1-PIO(11)-Pad34)") (class "Default")
      (node (ref "IC1") (pin "34") (pinfunction "PIO(11)_34") (pintype "bidirectional"))
    )
    (net (code "73") (name "unconnected-(IC1-RTS-Pad4)") (class "Default")
      (node (ref "IC1") (pin "4") (pinfunction "RTS_4") (pintype "bidirectional"))
    )
    (net (code "74") (name "unconnected-(IC1-SPI_CLK-Pad19)") (class "Default")
      (node (ref "IC1") (pin "19") (pinfunction "SPI_CLK_19") (pintype "bidirectional"))
    )
    (net (code "75") (name "unconnected-(IC1-SPI_CSB-Pad16)") (class "Default")
      (node (ref "IC1") (pin "16") (pinfunction "SPI_CSB_16") (pintype "bidirectional"))
    )
    (net (code "76") (name "unconnected-(IC1-SPI_MISO-Pad18)") (class "Default")
      (node (ref "IC1") (pin "18") (pinfunction "SPI_MISO_18") (pintype "bidirectional"))
    )
    (net (code "77") (name "unconnected-(IC1-SPI_MOSI-Pad17)") (class "Default")
      (node (ref "IC1") (pin "17") (pinfunction "SPI_MOSI_17") (pintype "bidirectional"))
    )
    (net (code "78") (name "unconnected-(IC1-USB_DN-Pad15)") (class "Default")
      (node (ref "IC1") (pin "15") (pinfunction "USB_DN_15") (pintype "bidirectional"))
    )
    (net (code "79") (name "unconnected-(IC1-USB_DP-Pad20)") (class "Default")
      (node (ref "IC1") (pin "20") (pinfunction "USB_DP_20") (pintype "bidirectional"))
    )
    (net (code "80") (name "unconnected-(IC2A-OSC_IN-Pad2)") (class "Default")
      (node (ref "IC2") (pin "2") (pinfunction "OSC_IN_2") (pintype "bidirectional"))
    )
    (net (code "81") (name "unconnected-(IC2A-OSC_OUT-Pad3)") (class "Default")
      (node (ref "IC2") (pin "3") (pinfunction "OSC_OUT_3") (pintype "bidirectional"))
    )
    (net (code "82") (name "unconnected-(T2-PadA1)") (class "Default")
      (node (ref "T2") (pin "A1") (pinfunction "A1_A1") (pintype "passive"))
    )
    (net (code "83") (name "unconnected-(T2-PadA2)") (class "Default")
      (node (ref "T2") (pin "A2") (pinfunction "A2_A2") (pintype "passive"))
    )
  )
)
